# Spectacle_Accelerometer_Input_Board.net
KiCad netlist of a schematic drawn in EAGLE
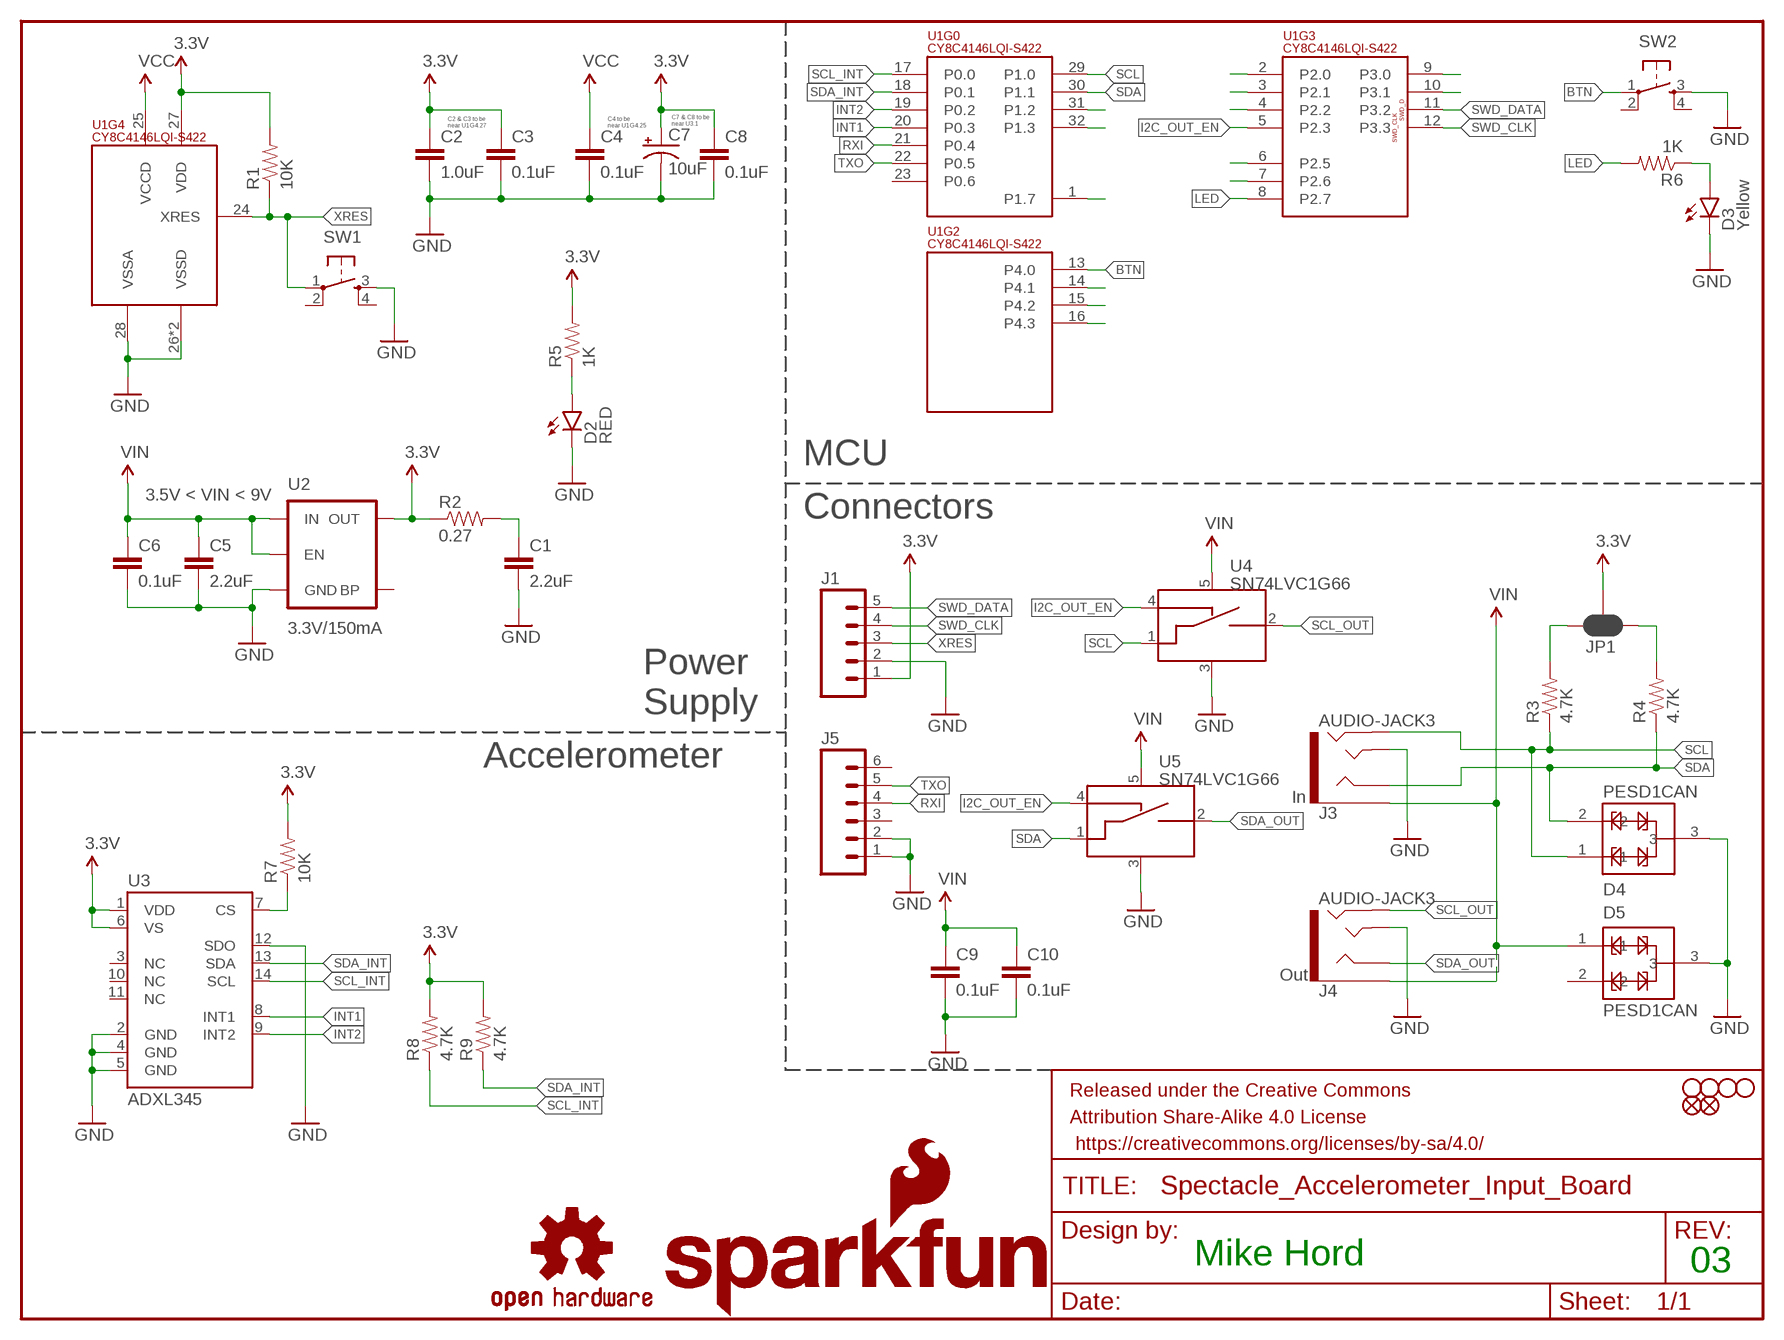
[diagram p0: schematic, sheet 1]

(export (version "E")
  (design (tool "Eeschema 10.0.6"))
  (components
    (comp (ref "C1")
      (value "2.2uF")
      (footprint "eagle-import:0603-CAP")
      (libsource (lib "eagle-import") (part "2.2UF-10V-20%(0603)"))
    )
    (comp (ref "C2")
      (value "1.0uF")
      (footprint "eagle-import:0402-CAP")
      (libsource (lib "eagle-import") (part "1.0UF-16V-10%(0402)"))
    )
    (comp (ref "C3")
      (value "0.1uF")
      (footprint "eagle-import:0402-CAP")
      (libsource (lib "eagle-import") (part "0.1UF-16V(+-10%)(0402)"))
    )
    (comp (ref "C4")
      (value "0.1uF")
      (footprint "eagle-import:0402-CAP")
      (libsource (lib "eagle-import") (part "0.1UF-16V(+-10%)(0402)"))
    )
    (comp (ref "C5")
      (value "2.2uF")
      (footprint "eagle-import:0603-CAP")
      (libsource (lib "eagle-import") (part "2.2UF-10V-20%(0603)"))
    )
    (comp (ref "C6")
      (value "0.1uF")
      (footprint "eagle-import:0402-CAP")
      (libsource (lib "eagle-import") (part "0.1UF-16V(+-10%)(0402)"))
    )
    (comp (ref "C7")
      (value "10uF")
      (footprint "eagle-import:EIA3216")
      (libsource (lib "eagle-import") (part "10UF-16V-10%(TANT)"))
    )
    (comp (ref "C8")
      (value "0.1uF")
      (footprint "eagle-import:0402-CAP")
      (libsource (lib "eagle-import") (part "0.1UF-16V(+-10%)(0402)"))
    )
    (comp (ref "C9")
      (value "0.1uF")
      (footprint "eagle-import:0402-CAP")
      (libsource (lib "eagle-import") (part "0.1UF-16V(+-10%)(0402)"))
    )
    (comp (ref "C10")
      (value "0.1uF")
      (footprint "eagle-import:0402-CAP")
      (libsource (lib "eagle-import") (part "0.1UF-16V(+-10%)(0402)"))
    )
    (comp (ref "D2")
      (value "RED")
      (footprint "eagle-import:LED-0603")
      (libsource (lib "eagle-import") (part "LED-RED0603"))
    )
    (comp (ref "D3")
      (value "Yellow")
      (footprint "eagle-import:LED-0603")
      (libsource (lib "eagle-import") (part "LED-YELLOW0603-SMART"))
    )
    (comp (ref "D4")
      (value "PESD1CAN")
      (footprint "eagle-import:SOT23-3")
      (libsource (lib "eagle-import") (part "PESD1CAN"))
    )
    (comp (ref "D5")
      (value "PESD1CAN")
      (footprint "eagle-import:SOT23-3")
      (libsource (lib "eagle-import") (part "PESD1CAN"))
    )
    (comp (ref "FD1")
      (value "FIDUCIALUFIDUCIAL")
      (footprint "eagle-import:MICRO-FIDUCIAL")
      (libsource (lib "eagle-import") (part "FIDUCIALUFIDUCIAL"))
    )
    (comp (ref "FD2")
      (value "FIDUCIALUFIDUCIAL")
      (footprint "eagle-import:MICRO-FIDUCIAL")
      (libsource (lib "eagle-import") (part "FIDUCIALUFIDUCIAL"))
    )
    (comp (ref "FRAME1")
      (value "FRAME-LETTER")
      (footprint "eagle-import:CREATIVE_COMMONS")
      (libsource (lib "eagle-import") (part "FRAME-LETTER"))
    )
    (comp (ref "H1")
      (value "STAND-OFF")
      (footprint "eagle-import:STAND-OFF")
      (libsource (lib "eagle-import") (part "STAND-OFF"))
    )
    (comp (ref "H2")
      (value "STAND-OFF")
      (footprint "eagle-import:STAND-OFF")
      (libsource (lib "eagle-import") (part "STAND-OFF"))
    )
    (comp (ref "H3")
      (value "STAND-OFF")
      (footprint "eagle-import:STAND-OFF")
      (libsource (lib "eagle-import") (part "STAND-OFF"))
    )
    (comp (ref "H4")
      (value "STAND-OFF")
      (footprint "eagle-import:STAND-OFF")
      (libsource (lib "eagle-import") (part "STAND-OFF"))
    )
    (comp (ref "J1")
      (value "M05NO_SILK")
      (footprint "eagle-import:1X05_NO_SILK")
      (libsource (lib "eagle-import") (part "M05NO_SILK"))
    )
    (comp (ref "J3")
      (value "AUDIO-JACK3")
      (footprint "eagle-import:AUDIO-JACK-TRRS-SMD")
      (libsource (lib "eagle-import") (part "AUDIO-JACK3"))
    )
    (comp (ref "J4")
      (value "AUDIO-JACK3")
      (footprint "eagle-import:AUDIO-JACK-TRRS-SMD")
      (libsource (lib "eagle-import") (part "AUDIO-JACK3"))
    )
    (comp (ref "J5")
      (value "M06NO_SILK_FEMALE_PTH")
      (footprint "eagle-import:1X06_NO_SILK")
      (libsource (lib "eagle-import") (part "M06NO_SILK_FEMALE_PTH"))
    )
    (comp (ref "JP1")
      (value "JUMPER-PAD-3-NC_BY_PASTE")
      (footprint "eagle-import:PAD-JUMPER-3-NC_BY_PASTE_YES_SILK_FULL_BOX")
      (libsource (lib "eagle-import") (part "JUMPER-PAD-3-NC_BY_PASTE"))
    )
    (comp (ref "LOGO1")
      (value "SFE_LOGO_NAME_FLAME.1_INCH")
      (footprint "eagle-import:SFE_LOGO_NAME_FLAME_.1")
      (libsource (lib "eagle-import") (part "SFE_LOGO_NAME_FLAME.1_INCH"))
    )
    (comp (ref "LOGO2")
      (value "OSHW-LOGOS")
      (footprint "eagle-import:OSHW-LOGO-S")
      (libsource (lib "eagle-import") (part "OSHW-LOGOS"))
    )
    (comp (ref "LOGO3")
      (value "OSHW-LOGOS")
      (footprint "eagle-import:OSHW-LOGO-S")
      (libsource (lib "eagle-import") (part "OSHW-LOGOS"))
    )
    (comp (ref "LOGO4")
      (value "SFE_LOGO_NAME_FLAME.1_INCH")
      (footprint "eagle-import:SFE_LOGO_NAME_FLAME_.1")
      (libsource (lib "eagle-import") (part "SFE_LOGO_NAME_FLAME.1_INCH"))
    )
    (comp (ref "R1")
      (value "10K")
      (footprint "eagle-import:0603-RES")
      (libsource (lib "eagle-import") (part "10KOHM-1/10W-1%(0603)0603"))
    )
    (comp (ref "R2")
      (value "0.27")
      (footprint "eagle-import:0603-RES")
      (libsource (lib "eagle-import") (part "0.27OHM-1/10W-1%(0603)"))
    )
    (comp (ref "R3")
      (value "4.7K")
      (footprint "eagle-import:0603-RES")
      (libsource (lib "eagle-import") (part "4.7KOHM-1/10W-1%(0603)"))
    )
    (comp (ref "R4")
      (value "4.7K")
      (footprint "eagle-import:0603-RES")
      (libsource (lib "eagle-import") (part "4.7KOHM-1/10W-1%(0603)"))
    )
    (comp (ref "R5")
      (value "1K")
      (footprint "eagle-import:0603-RES")
      (libsource (lib "eagle-import") (part "1KOHM-1/10W-1%(0603)"))
    )
    (comp (ref "R6")
      (value "1K")
      (footprint "eagle-import:0603-RES")
      (libsource (lib "eagle-import") (part "1KOHM-1/10W-1%(0603)"))
    )
    (comp (ref "R7")
      (value "10K")
      (footprint "eagle-import:0603-RES")
      (libsource (lib "eagle-import") (part "10KOHM-1/10W-1%(0603)0603"))
    )
    (comp (ref "R8")
      (value "4.7K")
      (footprint "eagle-import:0603-RES")
      (libsource (lib "eagle-import") (part "4.7KOHM-1/10W-1%(0603)"))
    )
    (comp (ref "R9")
      (value "4.7K")
      (footprint "eagle-import:0603-RES")
      (libsource (lib "eagle-import") (part "4.7KOHM-1/10W-1%(0603)"))
    )
    (comp (ref "SW1")
      (value "SWITCH_SPST_4_PINRECT")
      (footprint "eagle-import:TACTILE_SWITCH_SMD_4.6X2.8MM")
      (libsource (lib "eagle-import") (part "SWITCH_SPST_4_PINRECT"))
    )
    (comp (ref "SW2")
      (value "SWITCH_SPST_4_PINRECT")
      (footprint "eagle-import:TACTILE_SWITCH_SMD_4.6X2.8MM")
      (libsource (lib "eagle-import") (part "SWITCH_SPST_4_PINRECT"))
    )
    (comp (ref "U1")
      (value "CY8C4146LQI-S422")
      (footprint "eagle-import:QFN-32")
      (libsource (lib "eagle-import") (part "PSOC4_4100S_32QFN"))
    )
    (comp (ref "U2")
      (value "3.3V/150mA")
      (footprint "eagle-import:SOT23-5")
      (libsource (lib "eagle-import") (part "V_REG_MIC52053.3V"))
    )
    (comp (ref "U3")
      (value "ADXL345")
      (footprint "eagle-import:ADXL3451_1")
      (libsource (lib "eagle-import") (part "ADXL345{dblquote}"))
    )
    (comp (ref "U4")
      (value "SN74LVC1G66")
      (footprint "eagle-import:SOT23-5")
      (libsource (lib "eagle-import") (part "SN74LVC1G66_SPST_AMUX"))
    )
    (comp (ref "U5")
      (value "SN74LVC1G66")
      (footprint "eagle-import:SOT23-5")
      (libsource (lib "eagle-import") (part "SN74LVC1G66_SPST_AMUX"))
    )
  )
  (nets
    (net (code "1") (name "3.3V") (class "Default")
      (node (ref "C2") (pin "1") (pinfunction "1_1") (pintype "passive"))
      (node (ref "C3") (pin "1") (pinfunction "1_1") (pintype "passive"))
      (node (ref "C7") (pin "A") (pinfunction "+_A") (pintype "passive"))
      (node (ref "C8") (pin "1") (pinfunction "1_1") (pintype "passive"))
      (node (ref "J1") (pin "1") (pinfunction "1_1") (pintype "passive"))
      (node (ref "JP1") (pin "2") (pinfunction "2_2") (pintype "passive"))
      (node (ref "R1") (pin "2") (pinfunction "2_2") (pintype "passive"))
      (node (ref "R2") (pin "1") (pinfunction "1_1") (pintype "passive"))
      (node (ref "R5") (pin "2") (pinfunction "2_2") (pintype "passive"))
      (node (ref "R7") (pin "2") (pinfunction "2_2") (pintype "passive"))
      (node (ref "R8") (pin "2") (pinfunction "2_2") (pintype "passive"))
      (node (ref "R9") (pin "2") (pinfunction "2_2") (pintype "passive"))
      (node (ref "U1") (pin "27") (pinfunction "VDD_27") (pintype "bidirectional"))
      (node (ref "U2") (pin "5") (pinfunction "OUT_5") (pintype "passive"))
      (node (ref "U3") (pin "1") (pinfunction "VDD_1") (pintype "bidirectional"))
      (node (ref "U3") (pin "6") (pinfunction "VS_6") (pintype "bidirectional"))
    )
    (net (code "2") (name "BTN") (class "Default")
      (node (ref "SW2") (pin "1") (pinfunction "1_1") (pintype "passive"))
      (node (ref "U1") (pin "13") (pinfunction "P4.0_13") (pintype "bidirectional"))
    )
    (net (code "3") (name "GND") (class "Default")
      (node (ref "C1") (pin "2") (pinfunction "2_2") (pintype "passive"))
      (node (ref "C10") (pin "2") (pinfunction "2_2") (pintype "passive"))
      (node (ref "C2") (pin "2") (pinfunction "2_2") (pintype "passive"))
      (node (ref "C3") (pin "2") (pinfunction "2_2") (pintype "passive"))
      (node (ref "C4") (pin "2") (pinfunction "2_2") (pintype "passive"))
      (node (ref "C5") (pin "2") (pinfunction "2_2") (pintype "passive"))
      (node (ref "C6") (pin "2") (pinfunction "2_2") (pintype "passive"))
      (node (ref "C7") (pin "C") (pinfunction "-_C") (pintype "passive"))
      (node (ref "C8") (pin "2") (pinfunction "2_2") (pintype "passive"))
      (node (ref "C9") (pin "2") (pinfunction "2_2") (pintype "passive"))
      (node (ref "D2") (pin "C") (pinfunction "C_C") (pintype "passive"))
      (node (ref "D3") (pin "C") (pinfunction "C_C") (pintype "passive"))
      (node (ref "D4") (pin "3") (pinfunction "3_3") (pintype "bidirectional"))
      (node (ref "D5") (pin "3") (pinfunction "3_3") (pintype "bidirectional"))
      (node (ref "J1") (pin "2") (pinfunction "2_2") (pintype "passive"))
      (node (ref "J3") (pin "TIP") (pinfunction "TIP_TIP") (pintype "bidirectional"))
      (node (ref "J4") (pin "TIP") (pinfunction "TIP_TIP") (pintype "bidirectional"))
      (node (ref "J5") (pin "1") (pinfunction "1_1") (pintype "passive"))
      (node (ref "J5") (pin "2") (pinfunction "2_2") (pintype "passive"))
      (node (ref "SW1") (pin "3") (pinfunction "3_3") (pintype "passive"))
      (node (ref "SW2") (pin "3") (pinfunction "3_3") (pintype "passive"))
      (node (ref "U1") (pin "26") (pinfunction "VSSD_26") (pintype "bidirectional"))
      (node (ref "U1") (pin "28") (pinfunction "VSSA_28") (pintype "bidirectional"))
      (node (ref "U1") (pin "EP") (pinfunction "VSSD_EP") (pintype "bidirectional"))
      (node (ref "U2") (pin "2") (pinfunction "GND_2") (pintype "input"))
      (node (ref "U3") (pin "12") (pinfunction "SDO_12") (pintype "bidirectional"))
      (node (ref "U3") (pin "2") (pinfunction "GND_2") (pintype "bidirectional"))
      (node (ref "U3") (pin "4") (pinfunction "GND_4") (pintype "bidirectional"))
      (node (ref "U3") (pin "5") (pinfunction "GND_5") (pintype "bidirectional"))
      (node (ref "U4") (pin "3") (pinfunction "VSS_3") (pintype "bidirectional"))
      (node (ref "U5") (pin "3") (pinfunction "VSS_3") (pintype "bidirectional"))
    )
    (net (code "4") (name "I2C_OUT_EN") (class "Default")
      (node (ref "U1") (pin "5") (pinfunction "P2.3_5") (pintype "bidirectional"))
      (node (ref "U4") (pin "4") (pinfunction "CTRL_IN_4") (pintype "bidirectional"))
      (node (ref "U5") (pin "4") (pinfunction "CTRL_IN_4") (pintype "bidirectional"))
    )
    (net (code "5") (name "INT1") (class "Default")
      (node (ref "U1") (pin "20") (pinfunction "P0.3_20") (pintype "bidirectional"))
      (node (ref "U3") (pin "8") (pinfunction "INT1_8") (pintype "bidirectional"))
    )
    (net (code "6") (name "INT2") (class "Default")
      (node (ref "U1") (pin "19") (pinfunction "P0.2_19") (pintype "bidirectional"))
      (node (ref "U3") (pin "9") (pinfunction "INT2_9") (pintype "bidirectional"))
    )
    (net (code "7") (name "LED") (class "Default")
      (node (ref "R6") (pin "2") (pinfunction "2_2") (pintype "passive"))
      (node (ref "U1") (pin "8") (pinfunction "P2.7_8") (pintype "bidirectional"))
    )
    (net (code "8") (name "Net-(C1-Pad1)") (class "Default")
      (node (ref "C1") (pin "1") (pinfunction "1_1") (pintype "passive"))
      (node (ref "R2") (pin "2") (pinfunction "2_2") (pintype "passive"))
    )
    (net (code "9") (name "Net-(D2-PadA)") (class "Default")
      (node (ref "D2") (pin "A") (pinfunction "A_A") (pintype "passive"))
      (node (ref "R5") (pin "1") (pinfunction "1_1") (pintype "passive"))
    )
    (net (code "10") (name "Net-(D3-PadA)") (class "Default")
      (node (ref "D3") (pin "A") (pinfunction "A_A") (pintype "passive"))
      (node (ref "R6") (pin "1") (pinfunction "1_1") (pintype "passive"))
    )
    (net (code "11") (name "Net-(JP1-Pad1)") (class "Default")
      (node (ref "JP1") (pin "1") (pinfunction "1_1") (pintype "passive"))
      (node (ref "R4") (pin "2") (pinfunction "2_2") (pintype "passive"))
    )
    (net (code "12") (name "Net-(JP1-Pad3)") (class "Default")
      (node (ref "JP1") (pin "3") (pinfunction "3_3") (pintype "passive"))
      (node (ref "R3") (pin "2") (pinfunction "2_2") (pintype "passive"))
    )
    (net (code "13") (name "Net-(U3-CS)") (class "Default")
      (node (ref "R7") (pin "1") (pinfunction "1_1") (pintype "passive"))
      (node (ref "U3") (pin "7") (pinfunction "CS_7") (pintype "bidirectional"))
    )
    (net (code "14") (name "RXI") (class "Default")
      (node (ref "J5") (pin "4") (pinfunction "4_4") (pintype "passive"))
      (node (ref "U1") (pin "21") (pinfunction "P0.4_21") (pintype "bidirectional"))
    )
    (net (code "15") (name "SCL") (class "Default")
      (node (ref "D4") (pin "1") (pinfunction "1_1") (pintype "bidirectional"))
      (node (ref "J3") (pin "RING2") (pinfunction "RING2_RING2") (pintype "bidirectional"))
      (node (ref "R3") (pin "1") (pinfunction "1_1") (pintype "passive"))
      (node (ref "U1") (pin "29") (pinfunction "P1.0_29") (pintype "bidirectional"))
      (node (ref "U4") (pin "1") (pinfunction "A_IN_1") (pintype "bidirectional"))
    )
    (net (code "16") (name "SCL_INT") (class "Default")
      (node (ref "R8") (pin "1") (pinfunction "1_1") (pintype "passive"))
      (node (ref "U1") (pin "17") (pinfunction "P0.0_17") (pintype "bidirectional"))
      (node (ref "U3") (pin "14") (pinfunction "SCL_14") (pintype "bidirectional"))
    )
    (net (code "17") (name "SCL_OUT") (class "Default")
      (node (ref "J4") (pin "RING2") (pinfunction "RING2_RING2") (pintype "bidirectional"))
      (node (ref "U4") (pin "2") (pinfunction "A_OUT_2") (pintype "bidirectional"))
    )
    (net (code "18") (name "SDA") (class "Default")
      (node (ref "D4") (pin "2") (pinfunction "2_2") (pintype "bidirectional"))
      (node (ref "J3") (pin "RING1") (pinfunction "RING1_RING1") (pintype "bidirectional"))
      (node (ref "R4") (pin "1") (pinfunction "1_1") (pintype "passive"))
      (node (ref "U1") (pin "30") (pinfunction "P1.1_30") (pintype "bidirectional"))
      (node (ref "U5") (pin "1") (pinfunction "A_IN_1") (pintype "bidirectional"))
    )
    (net (code "19") (name "SDA_INT") (class "Default")
      (node (ref "R9") (pin "1") (pinfunction "1_1") (pintype "passive"))
      (node (ref "U1") (pin "18") (pinfunction "P0.1_18") (pintype "bidirectional"))
      (node (ref "U3") (pin "13") (pinfunction "SDA_13") (pintype "bidirectional"))
    )
    (net (code "20") (name "SDA_OUT") (class "Default")
      (node (ref "J4") (pin "RING1") (pinfunction "RING1_RING1") (pintype "bidirectional"))
      (node (ref "U5") (pin "2") (pinfunction "A_OUT_2") (pintype "bidirectional"))
    )
    (net (code "21") (name "SWD_CLK") (class "Default")
      (node (ref "J1") (pin "4") (pinfunction "4_4") (pintype "passive"))
      (node (ref "U1") (pin "12") (pinfunction "P3.3_12") (pintype "bidirectional"))
    )
    (net (code "22") (name "SWD_DATA") (class "Default")
      (node (ref "J1") (pin "5") (pinfunction "5_5") (pintype "passive"))
      (node (ref "U1") (pin "11") (pinfunction "P3.2_11") (pintype "bidirectional"))
    )
    (net (code "23") (name "TXO") (class "Default")
      (node (ref "J5") (pin "5") (pinfunction "5_5") (pintype "passive"))
      (node (ref "U1") (pin "22") (pinfunction "P0.5_22") (pintype "bidirectional"))
    )
    (net (code "24") (name "VCC") (class "Default")
      (node (ref "C4") (pin "1") (pinfunction "1_1") (pintype "passive"))
      (node (ref "U1") (pin "25") (pinfunction "VCCD_25") (pintype "bidirectional"))
    )
    (net (code "25") (name "VIN") (class "Default")
      (node (ref "C10") (pin "1") (pinfunction "1_1") (pintype "passive"))
      (node (ref "C5") (pin "1") (pinfunction "1_1") (pintype "passive"))
      (node (ref "C6") (pin "1") (pinfunction "1_1") (pintype "passive"))
      (node (ref "C9") (pin "1") (pinfunction "1_1") (pintype "passive"))
      (node (ref "D5") (pin "1") (pinfunction "1_1") (pintype "bidirectional"))
      (node (ref "J3") (pin "EARTH") (pinfunction "EARTH_EARTH") (pintype "bidirectional"))
      (node (ref "J4") (pin "EARTH") (pinfunction "EARTH_EARTH") (pintype "bidirectional"))
      (node (ref "U2") (pin "1") (pinfunction "IN_1") (pintype "input"))
      (node (ref "U2") (pin "3") (pinfunction "EN_3") (pintype "input"))
      (node (ref "U4") (pin "5") (pinfunction "VCC_5") (pintype "bidirectional"))
      (node (ref "U5") (pin "5") (pinfunction "VCC_5") (pintype "bidirectional"))
    )
    (net (code "26") (name "XRES") (class "Default")
      (node (ref "J1") (pin "3") (pinfunction "3_3") (pintype "passive"))
      (node (ref "R1") (pin "1") (pinfunction "1_1") (pintype "passive"))
      (node (ref "SW1") (pin "1") (pinfunction "1_1") (pintype "passive"))
      (node (ref "U1") (pin "24") (pinfunction "XRES_24") (pintype "bidirectional"))
    )
    (net (code "27") (name "unconnected-(D5-Pad2)") (class "Default")
      (node (ref "D5") (pin "2") (pinfunction "2_2") (pintype "bidirectional"))
    )
    (net (code "28") (name "unconnected-(J5-Pad3)") (class "Default")
      (node (ref "J5") (pin "3") (pinfunction "3_3") (pintype "passive"))
    )
    (net (code "29") (name "unconnected-(J5-Pad6)") (class "Default")
      (node (ref "J5") (pin "6") (pinfunction "6_6") (pintype "passive"))
    )
    (net (code "30") (name "unconnected-(SW1-Pad2)") (class "Default")
      (node (ref "SW1") (pin "2") (pinfunction "2_2") (pintype "passive"))
    )
    (net (code "31") (name "unconnected-(SW1-Pad4)") (class "Default")
      (node (ref "SW1") (pin "4") (pinfunction "4_4") (pintype "passive"))
    )
    (net (code "32") (name "unconnected-(SW2-Pad2)") (class "Default")
      (node (ref "SW2") (pin "2") (pinfunction "2_2") (pintype "passive"))
    )
    (net (code "33") (name "unconnected-(SW2-Pad4)") (class "Default")
      (node (ref "SW2") (pin "4") (pinfunction "4_4") (pintype "passive"))
    )
    (net (code "34") (name "unconnected-(U1A-P0.6-Pad23)") (class "Default")
      (node (ref "U1") (pin "23") (pinfunction "P0.6_23") (pintype "bidirectional"))
    )
    (net (code "35") (name "unconnected-(U1A-P1.2-Pad31)") (class "Default")
      (node (ref "U1") (pin "31") (pinfunction "P1.2_31") (pintype "bidirectional"))
    )
    (net (code "36") (name "unconnected-(U1A-P1.3-Pad32)") (class "Default")
      (node (ref "U1") (pin "32") (pinfunction "P1.3_32") (pintype "bidirectional"))
    )
    (net (code "37") (name "unconnected-(U1A-P1.7-Pad1)") (class "Default")
      (node (ref "U1") (pin "1") (pinfunction "P1.7_1") (pintype "bidirectional"))
    )
    (net (code "38") (name "unconnected-(U1B-P4.1-Pad14)") (class "Default")
      (node (ref "U1") (pin "14") (pinfunction "P4.1_14") (pintype "bidirectional"))
    )
    (net (code "39") (name "unconnected-(U1B-P4.2-Pad15)") (class "Default")
      (node (ref "U1") (pin "15") (pinfunction "P4.2_15") (pintype "bidirectional"))
    )
    (net (code "40") (name "unconnected-(U1B-P4.3-Pad16)") (class "Default")
      (node (ref "U1") (pin "16") (pinfunction "P4.3_16") (pintype "bidirectional"))
    )
    (net (code "41") (name "unconnected-(U1C-P2.0-Pad2)") (class "Default")
      (node (ref "U1") (pin "2") (pinfunction "P2.0_2") (pintype "bidirectional"))
    )
    (net (code "42") (name "unconnected-(U1C-P2.1-Pad3)") (class "Default")
      (node (ref "U1") (pin "3") (pinfunction "P2.1_3") (pintype "bidirectional"))
    )
    (net (code "43") (name "unconnected-(U1C-P2.2-Pad4)") (class "Default")
      (node (ref "U1") (pin "4") (pinfunction "P2.2_4") (pintype "bidirectional"))
    )
    (net (code "44") (name "unconnected-(U1C-P2.5-Pad6)") (class "Default")
      (node (ref "U1") (pin "6") (pinfunction "P2.5_6") (pintype "bidirectional"))
    )
    (net (code "45") (name "unconnected-(U1C-P2.6-Pad7)") (class "Default")
      (node (ref "U1") (pin "7") (pinfunction "P2.6_7") (pintype "bidirectional"))
    )
    (net (code "46") (name "unconnected-(U1C-P3.0-Pad9)") (class "Default")
      (node (ref "U1") (pin "9") (pinfunction "P3.0_9") (pintype "bidirectional"))
    )
    (net (code "47") (name "unconnected-(U1C-P3.1-Pad10)") (class "Default")
      (node (ref "U1") (pin "10") (pinfunction "P3.1_10") (pintype "bidirectional"))
    )
    (net (code "48") (name "unconnected-(U2-BP-Pad4)") (class "Default")
      (node (ref "U2") (pin "4") (pinfunction "BP_4") (pintype "input"))
    )
    (net (code "49") (name "unconnected-(U3-NC-Pad3)") (class "Default")
      (node (ref "U3") (pin "3") (pinfunction "NC_3") (pintype "bidirectional"))
    )
    (net (code "50") (name "unconnected-(U3-NC-Pad10)") (class "Default")
      (node (ref "U3") (pin "10") (pinfunction "NC_10") (pintype "bidirectional"))
    )
    (net (code "51") (name "unconnected-(U3-NC-Pad11)") (class "Default")
      (node (ref "U3") (pin "11") (pinfunction "NC_11") (pintype "bidirectional"))
    )
  )
)
